# GIP-BH1750.net
KiCad netlist of a schematic drawn in EAGLE
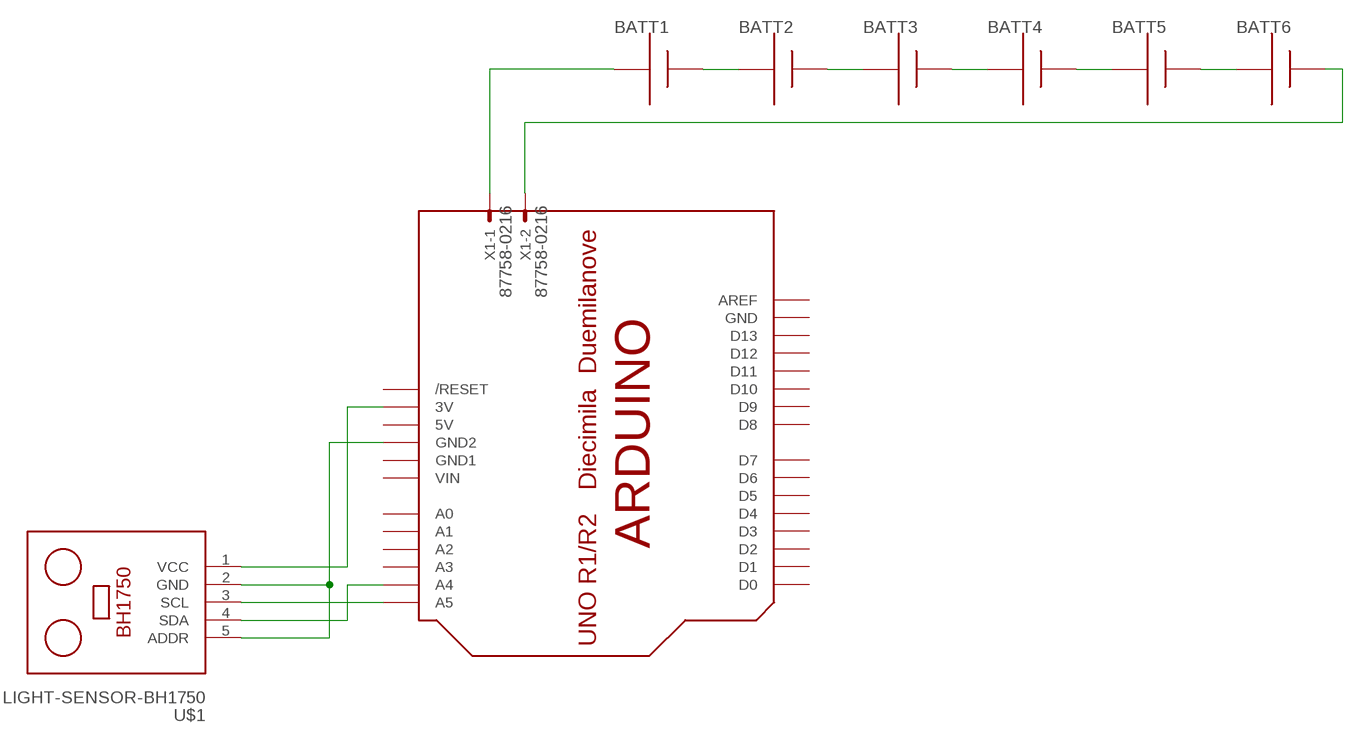
[diagram p0: schematic, sheet 1]

(export (version "E")
  (design (tool "Eeschema 10.0.6"))
  (components
    (comp (ref "BATT1")
      (value "AAA")
      (footprint "eagle-import:12BH412")
      (libsource (lib "eagle-import") (part "AAA"))
    )
    (comp (ref "BATT2")
      (value "AAA")
      (footprint "eagle-import:12BH412")
      (libsource (lib "eagle-import") (part "AAA"))
    )
    (comp (ref "BATT3")
      (value "AAA")
      (footprint "eagle-import:12BH412")
      (libsource (lib "eagle-import") (part "AAA"))
    )
    (comp (ref "BATT4")
      (value "AAA")
      (footprint "eagle-import:12BH412")
      (libsource (lib "eagle-import") (part "AAA"))
    )
    (comp (ref "BATT5")
      (value "AAA")
      (footprint "eagle-import:12BH412")
      (libsource (lib "eagle-import") (part "AAA"))
    )
    (comp (ref "BATT6")
      (value "AAA")
      (footprint "eagle-import:12BH412")
      (libsource (lib "eagle-import") (part "AAA"))
    )
    (comp (ref "U$1")
      (value "LIGHT-SENSOR-BH1750")
      (footprint "eagle-import:LIGHT-SENSOR-BH1750")
      (libsource (lib "eagle-import") (part "LIGHT-SENSOR-BH1750"))
    )
    (comp (ref "U$2")
      (value "ARDUINO-BPLACE")
      (footprint "eagle-import:ARDUINO-BPLACE")
      (libsource (lib "eagle-import") (part "ARDUINO-BPLACE"))
    )
    (comp (ref "X1")
      (value "87758-0216")
      (footprint "eagle-import:87758-0216")
      (fields (field (name "MF") "MOLEX"))
      (libsource (lib "eagle-import") (part "87758-0216"))
    )
  )
  (nets
    (net (code "1") (name "/5V") (class "Default")
      (node (ref "U$2") (pin "5V") (pinfunction "5V_5V") (pintype "power_in"))
    )
    (net (code "2") (name "/GND") (class "Default")
      (node (ref "U$2") (pin "GND") (pinfunction "GND_GND") (pintype "power_in"))
    )
    (net (code "3") (name "/GND1") (class "Default")
      (node (ref "U$2") (pin "GND1") (pinfunction "GND1_GND1") (pintype "power_in"))
    )
    (net (code "4") (name "/VIN") (class "Default")
      (node (ref "U$2") (pin "VIN") (pinfunction "VIN_VIN") (pintype "power_in"))
    )
    (net (code "5") (name "Net-(BATT1-Pad+)") (class "Default")
      (node (ref "BATT1") (pin "+") (pinfunction "+_+") (pintype "bidirectional"))
      (node (ref "BATT2") (pin "-") (pinfunction "-_-") (pintype "bidirectional"))
    )
    (net (code "6") (name "Net-(BATT2-Pad+)") (class "Default")
      (node (ref "BATT2") (pin "+") (pinfunction "+_+") (pintype "bidirectional"))
      (node (ref "BATT3") (pin "-") (pinfunction "-_-") (pintype "bidirectional"))
    )
    (net (code "7") (name "Net-(BATT3-Pad+)") (class "Default")
      (node (ref "BATT3") (pin "+") (pinfunction "+_+") (pintype "bidirectional"))
      (node (ref "BATT4") (pin "-") (pinfunction "-_-") (pintype "bidirectional"))
    )
    (net (code "8") (name "Net-(BATT4-Pad+)") (class "Default")
      (node (ref "BATT4") (pin "+") (pinfunction "+_+") (pintype "bidirectional"))
      (node (ref "BATT5") (pin "-") (pinfunction "-_-") (pintype "bidirectional"))
    )
    (net (code "9") (name "Net-(BATT5-Pad+)") (class "Default")
      (node (ref "BATT5") (pin "+") (pinfunction "+_+") (pintype "bidirectional"))
      (node (ref "BATT6") (pin "-") (pinfunction "-_-") (pintype "bidirectional"))
    )
    (net (code "10") (name "Net-(U$1-ADDR)") (class "Default")
      (node (ref "U$1") (pin "2") (pinfunction "GND_2") (pintype "power_in"))
      (node (ref "U$1") (pin "5") (pinfunction "ADDR_5") (pintype "bidirectional"))
      (node (ref "U$2") (pin "GND2") (pinfunction "GND2_GND2") (pintype "power_in"))
    )
    (net (code "11") (name "Net-(U$1-SCL)") (class "Default")
      (node (ref "U$1") (pin "3") (pinfunction "SCL_3") (pintype "bidirectional"))
      (node (ref "U$2") (pin "A5") (pinfunction "A5_A5") (pintype "bidirectional"))
    )
    (net (code "12") (name "Net-(U$1-SDA)") (class "Default")
      (node (ref "U$1") (pin "4") (pinfunction "SDA_4") (pintype "bidirectional"))
      (node (ref "U$2") (pin "A4") (pinfunction "A4_A4") (pintype "bidirectional"))
    )
    (net (code "13") (name "Net-(U$1-VCC)") (class "Default")
      (node (ref "U$1") (pin "1") (pinfunction "VCC_1") (pintype "power_in"))
      (node (ref "U$2") (pin "3V") (pinfunction "3V_3V") (pintype "power_in"))
    )
    (net (code "14") (name "Net-(X1A-S)") (class "Default")
      (node (ref "BATT1") (pin "-") (pinfunction "-_-") (pintype "bidirectional"))
      (node (ref "X1") (pin "1") (pinfunction "S_1") (pintype "passive"))
    )
    (net (code "15") (name "Net-(X1B-S)") (class "Default")
      (node (ref "BATT6") (pin "+") (pinfunction "+_+") (pintype "bidirectional"))
      (node (ref "X1") (pin "2") (pinfunction "S_2") (pintype "passive"))
    )
    (net (code "16") (name "unconnected-(U$2-PadA0)") (class "Default")
      (node (ref "U$2") (pin "A0") (pinfunction "A0_A0") (pintype "bidirectional"))
    )
    (net (code "17") (name "unconnected-(U$2-PadA1)") (class "Default")
      (node (ref "U$2") (pin "A1") (pinfunction "A1_A1") (pintype "bidirectional"))
    )
    (net (code "18") (name "unconnected-(U$2-PadA2)") (class "Default")
      (node (ref "U$2") (pin "A2") (pinfunction "A2_A2") (pintype "bidirectional"))
    )
    (net (code "19") (name "unconnected-(U$2-PadA3)") (class "Default")
      (node (ref "U$2") (pin "A3") (pinfunction "A3_A3") (pintype "bidirectional"))
    )
    (net (code "20") (name "unconnected-(U$2-PadAREF)") (class "Default")
      (node (ref "U$2") (pin "AREF") (pinfunction "AREF_AREF") (pintype "bidirectional"))
    )
    (net (code "21") (name "unconnected-(U$2-PadD0)") (class "Default")
      (node (ref "U$2") (pin "D0") (pinfunction "D0_D0") (pintype "bidirectional"))
    )
    (net (code "22") (name "unconnected-(U$2-PadD1)") (class "Default")
      (node (ref "U$2") (pin "D1") (pinfunction "D1_D1") (pintype "bidirectional"))
    )
    (net (code "23") (name "unconnected-(U$2-PadD2)") (class "Default")
      (node (ref "U$2") (pin "D2") (pinfunction "D2_D2") (pintype "bidirectional"))
    )
    (net (code "24") (name "unconnected-(U$2-PadD3)") (class "Default")
      (node (ref "U$2") (pin "D3") (pinfunction "D3_D3") (pintype "bidirectional"))
    )
    (net (code "25") (name "unconnected-(U$2-PadD4)") (class "Default")
      (node (ref "U$2") (pin "D4") (pinfunction "D4_D4") (pintype "bidirectional"))
    )
    (net (code "26") (name "unconnected-(U$2-PadD5)") (class "Default")
      (node (ref "U$2") (pin "D5") (pinfunction "D5_D5") (pintype "bidirectional"))
    )
    (net (code "27") (name "unconnected-(U$2-PadD6)") (class "Default")
      (node (ref "U$2") (pin "D6") (pinfunction "D6_D6") (pintype "bidirectional"))
    )
    (net (code "28") (name "unconnected-(U$2-PadD7)") (class "Default")
      (node (ref "U$2") (pin "D7") (pinfunction "D7_D7") (pintype "bidirectional"))
    )
    (net (code "29") (name "unconnected-(U$2-PadD8)") (class "Default")
      (node (ref "U$2") (pin "D8") (pinfunction "D8_D8") (pintype "bidirectional"))
    )
    (net (code "30") (name "unconnected-(U$2-PadD9)") (class "Default")
      (node (ref "U$2") (pin "D9") (pinfunction "D9_D9") (pintype "bidirectional"))
    )
    (net (code "31") (name "unconnected-(U$2-PadD10)") (class "Default")
      (node (ref "U$2") (pin "D10") (pinfunction "D10_D10") (pintype "bidirectional"))
    )
    (net (code "32") (name "unconnected-(U$2-PadD11)") (class "Default")
      (node (ref "U$2") (pin "D11") (pinfunction "D11_D11") (pintype "bidirectional"))
    )
    (net (code "33") (name "unconnected-(U$2-PadD12)") (class "Default")
      (node (ref "U$2") (pin "D12") (pinfunction "D12_D12") (pintype "bidirectional"))
    )
    (net (code "34") (name "unconnected-(U$2-PadD13)") (class "Default")
      (node (ref "U$2") (pin "D13") (pinfunction "D13_D13") (pintype "bidirectional"))
    )
    (net (code "35") (name "unconnected-(U$2-{slash}RESET-PadRESET)") (class "Default")
      (node (ref "U$2") (pin "RESET") (pinfunction "/RESET_RESET") (pintype "bidirectional"))
    )
  )
)
